# TT7N_v1_2.net
KiCad netlist of a schematic drawn in EAGLE
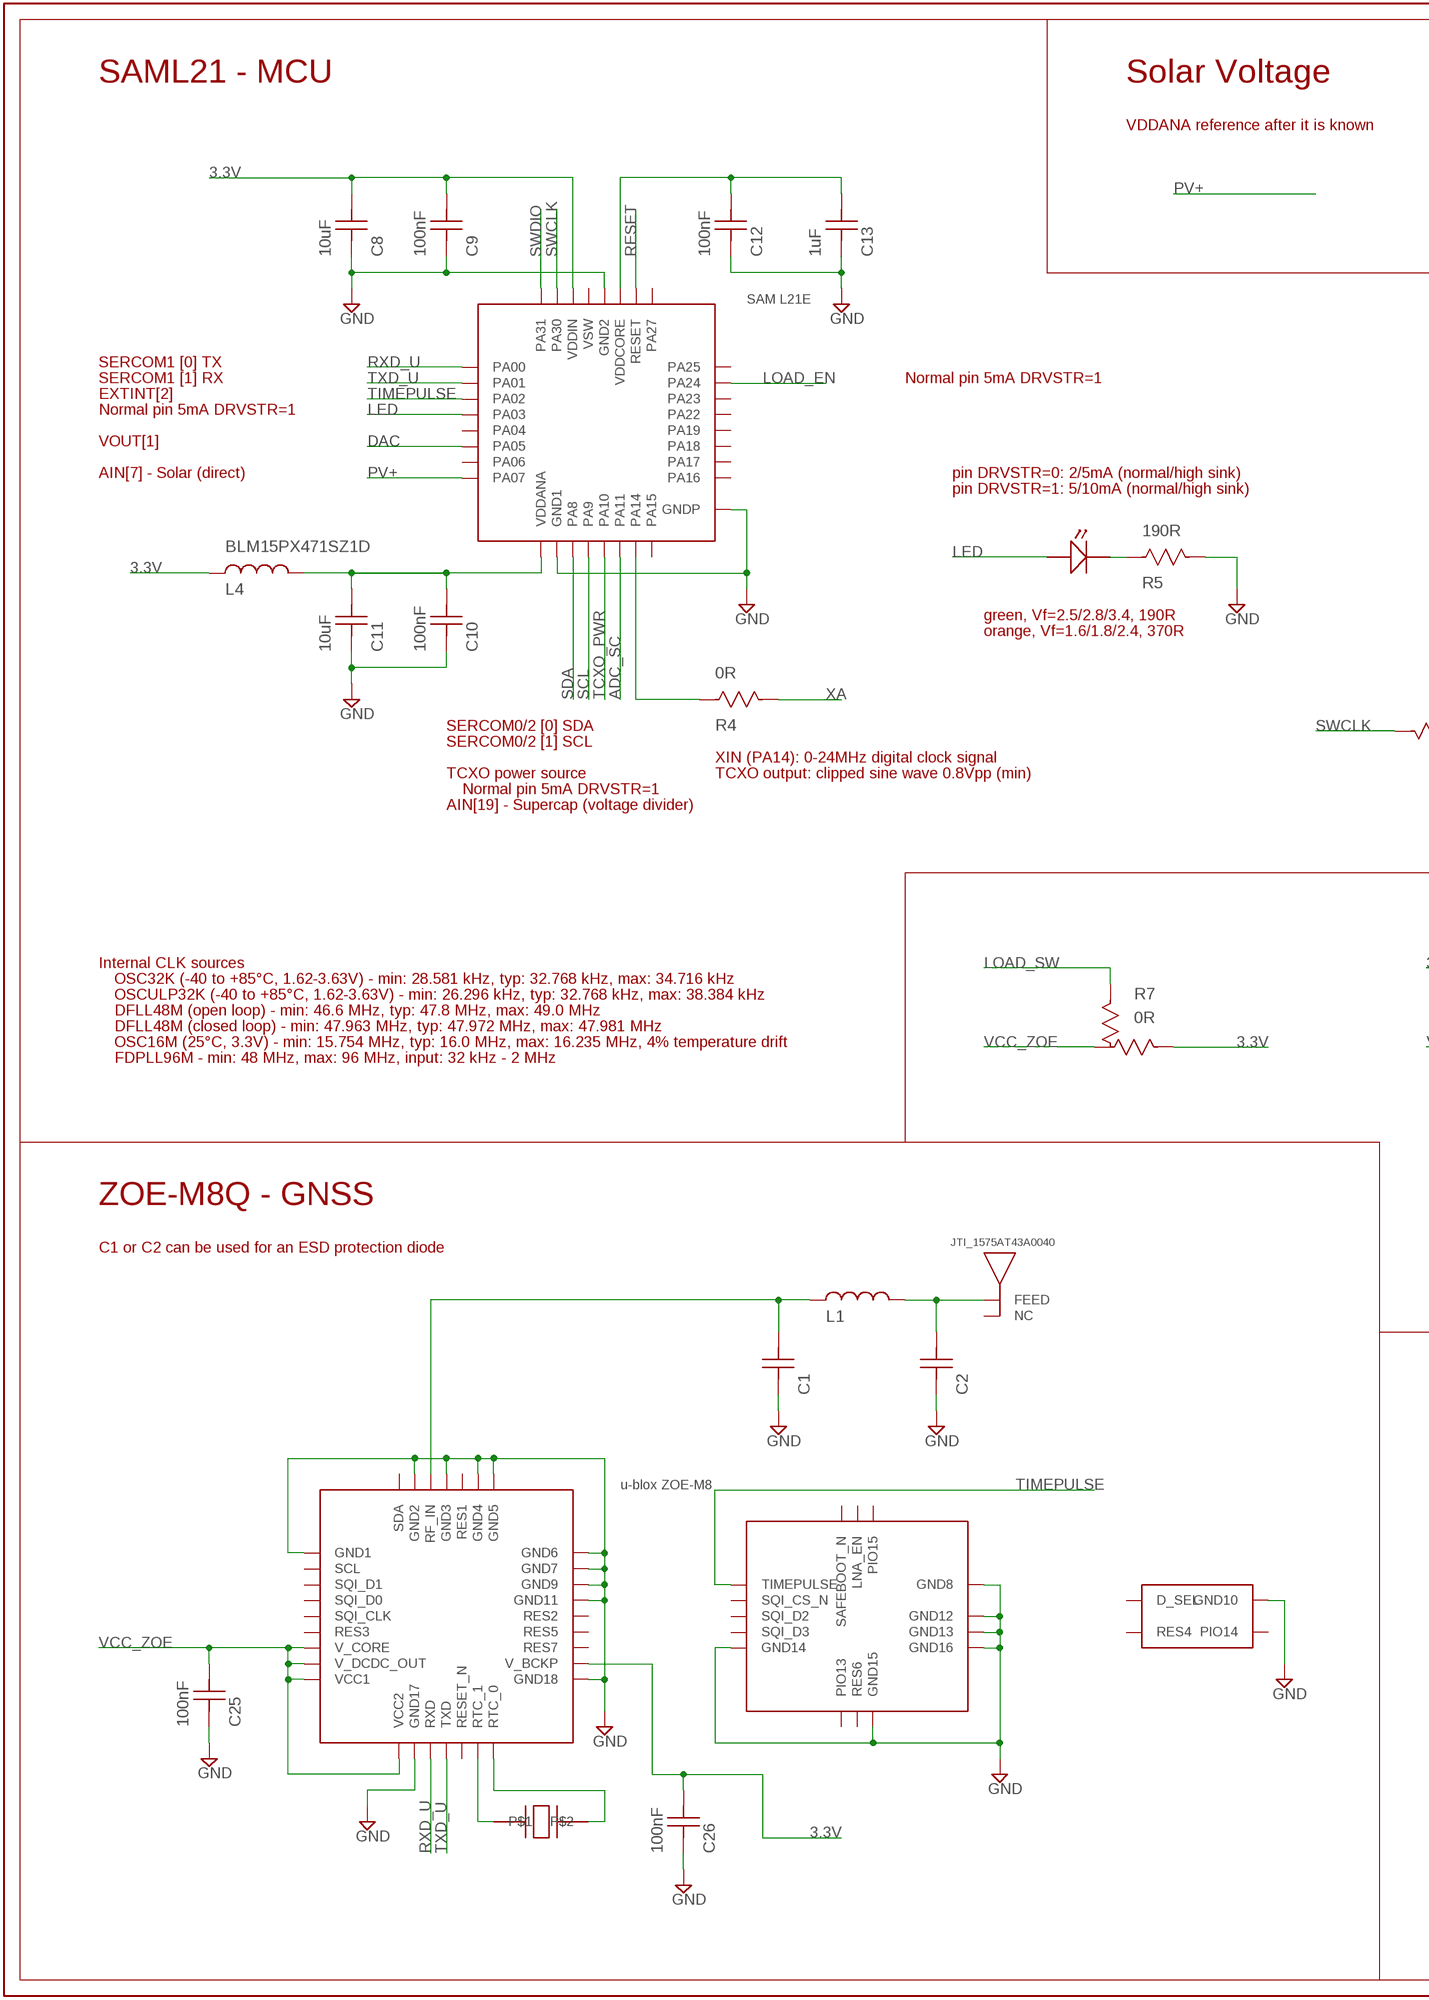
[diagram p0: schematic, sheet 1, part 1 of 2]
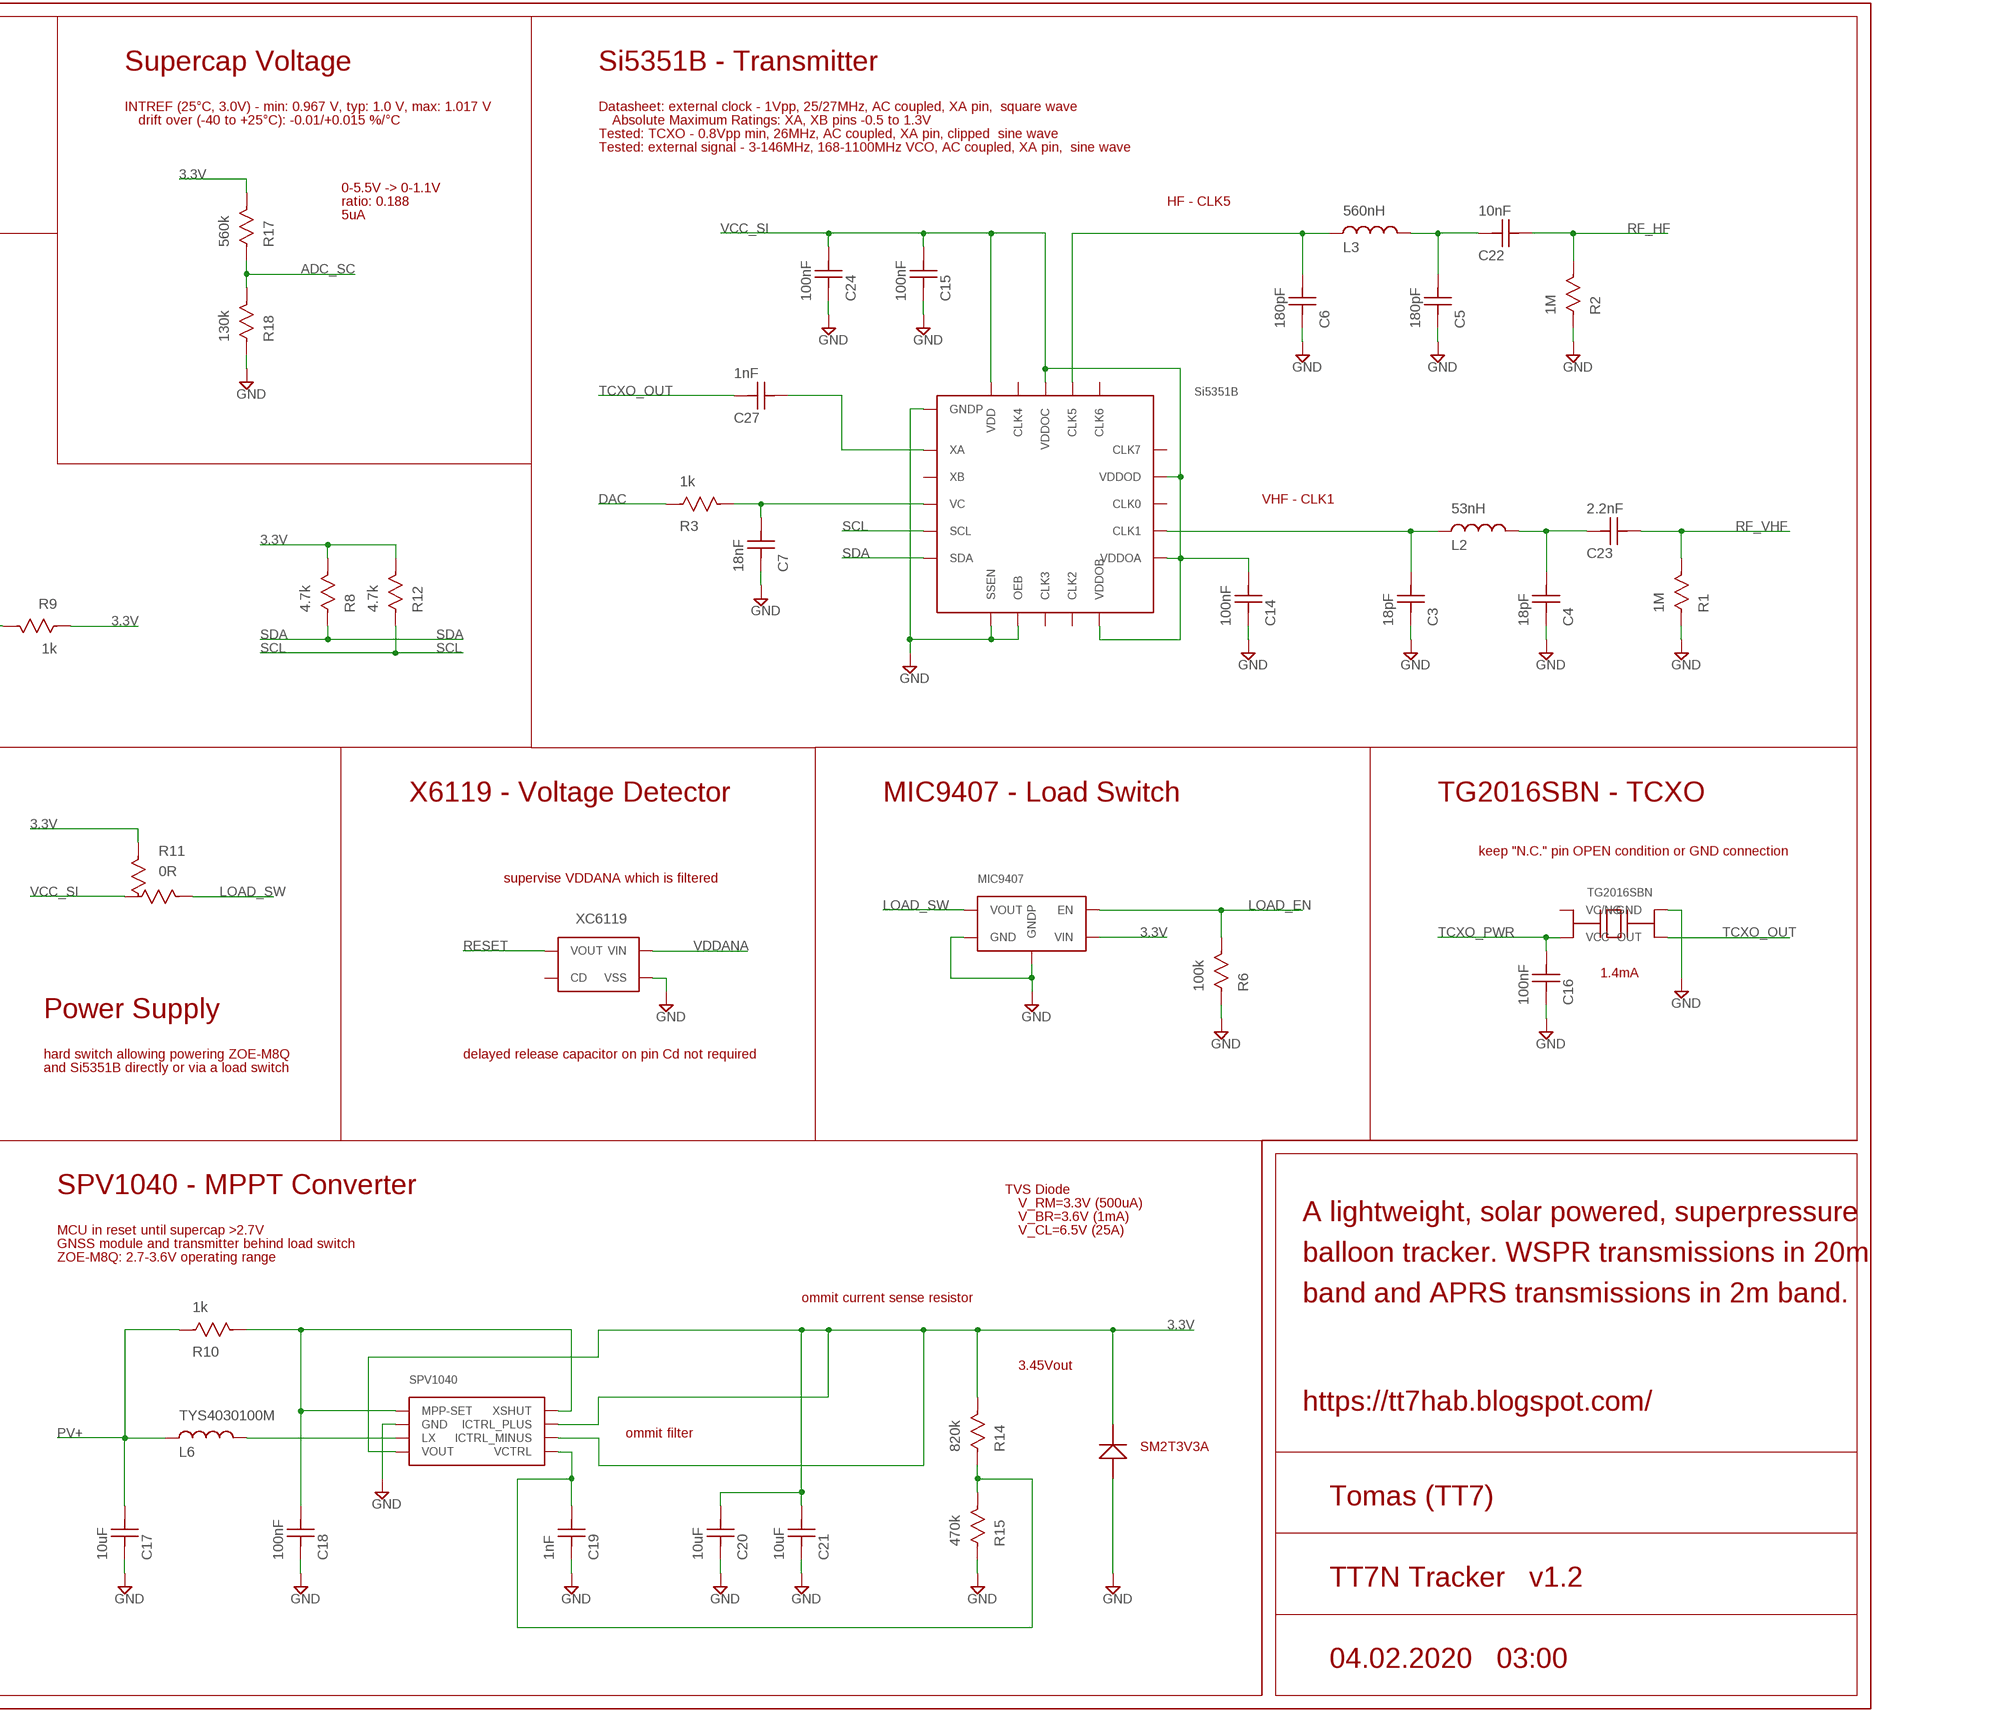
[diagram p1: schematic, sheet 1, part 2 of 2]

(export (version "E")
  (design (tool "Eeschema 10.0.6"))
  (components
    (comp (ref "ANT1")
      (value "JTI_1575AT43A0040")
      (footprint "eagle-import:JTI_1575AT43A0040")
      (libsource (lib "eagle-import") (part "JTI_1575AT43A0040"))
    )
    (comp (ref "C1")
      (value "CAP0402")
      (footprint "eagle-import:CAP0402")
      (libsource (lib "eagle-import") (part "CAP0402"))
    )
    (comp (ref "C2")
      (value "CAP0402")
      (footprint "eagle-import:CAP0402")
      (libsource (lib "eagle-import") (part "CAP0402"))
    )
    (comp (ref "C3")
      (value "18pF")
      (footprint "eagle-import:CAP0402")
      (libsource (lib "eagle-import") (part "CAP0402"))
    )
    (comp (ref "C4")
      (value "18pF")
      (footprint "eagle-import:CAP0402")
      (libsource (lib "eagle-import") (part "CAP0402"))
    )
    (comp (ref "C5")
      (value "180pF")
      (footprint "eagle-import:CAP0402")
      (libsource (lib "eagle-import") (part "CAP0402"))
    )
    (comp (ref "C6")
      (value "180pF")
      (footprint "eagle-import:CAP0402")
      (libsource (lib "eagle-import") (part "CAP0402"))
    )
    (comp (ref "C7")
      (value "18nF")
      (footprint "eagle-import:CAP0402")
      (libsource (lib "eagle-import") (part "CAP0402"))
    )
    (comp (ref "C8")
      (value "10uF")
      (footprint "eagle-import:CAP0402")
      (libsource (lib "eagle-import") (part "CAP0402"))
    )
    (comp (ref "C9")
      (value "100nF")
      (footprint "eagle-import:CAP0402")
      (libsource (lib "eagle-import") (part "CAP0402"))
    )
    (comp (ref "C10")
      (value "100nF")
      (footprint "eagle-import:CAP0402")
      (libsource (lib "eagle-import") (part "CAP0402"))
    )
    (comp (ref "C11")
      (value "10uF")
      (footprint "eagle-import:CAP0402")
      (libsource (lib "eagle-import") (part "CAP0402"))
    )
    (comp (ref "C12")
      (value "100nF")
      (footprint "eagle-import:CAP0402")
      (libsource (lib "eagle-import") (part "CAP0402"))
    )
    (comp (ref "C13")
      (value "1uF")
      (footprint "eagle-import:CAP0402")
      (libsource (lib "eagle-import") (part "CAP0402"))
    )
    (comp (ref "C14")
      (value "100nF")
      (footprint "eagle-import:CAP0402")
      (libsource (lib "eagle-import") (part "CAP0402"))
    )
    (comp (ref "C15")
      (value "100nF")
      (footprint "eagle-import:CAP0402")
      (libsource (lib "eagle-import") (part "CAP0402"))
    )
    (comp (ref "C16")
      (value "100nF")
      (footprint "eagle-import:CAP0402")
      (libsource (lib "eagle-import") (part "CAP0402"))
    )
    (comp (ref "C17")
      (value "10uF")
      (footprint "eagle-import:CAP0402")
      (libsource (lib "eagle-import") (part "CAP0402"))
    )
    (comp (ref "C18")
      (value "100nF")
      (footprint "eagle-import:CAP0402")
      (libsource (lib "eagle-import") (part "CAP0402"))
    )
    (comp (ref "C19")
      (value "1nF")
      (footprint "eagle-import:CAP0402")
      (libsource (lib "eagle-import") (part "CAP0402"))
    )
    (comp (ref "C20")
      (value "10uF")
      (footprint "eagle-import:CAP0402")
      (libsource (lib "eagle-import") (part "CAP0402"))
    )
    (comp (ref "C21")
      (value "10uF")
      (footprint "eagle-import:CAP0402")
      (libsource (lib "eagle-import") (part "CAP0402"))
    )
    (comp (ref "C22")
      (value "10nF")
      (footprint "eagle-import:CAP0402")
      (libsource (lib "eagle-import") (part "CAP0402"))
    )
    (comp (ref "C23")
      (value "2.2nF")
      (footprint "eagle-import:CAP0402")
      (libsource (lib "eagle-import") (part "CAP0402"))
    )
    (comp (ref "C24")
      (value "100nF")
      (footprint "eagle-import:CAP0402")
      (libsource (lib "eagle-import") (part "CAP0402"))
    )
    (comp (ref "C25")
      (value "100nF")
      (footprint "eagle-import:CAP0402")
      (libsource (lib "eagle-import") (part "CAP0402"))
    )
    (comp (ref "C26")
      (value "100nF")
      (footprint "eagle-import:CAP0402")
      (libsource (lib "eagle-import") (part "CAP0402"))
    )
    (comp (ref "C27")
      (value "1nF")
      (footprint "eagle-import:CAP0402")
      (libsource (lib "eagle-import") (part "CAP0402"))
    )
    (comp (ref "D1")
      (value "SM2T3V3A")
      (footprint "eagle-import:SM2T3V3A")
      (libsource (lib "eagle-import") (part "SM2T3V3A"))
    )
    (comp (ref "L1")
      (value "IND0402")
      (footprint "eagle-import:IND0402")
      (libsource (lib "eagle-import") (part "IND0402"))
    )
    (comp (ref "L2")
      (value "53nH")
      (footprint "eagle-import:IND0402")
      (libsource (lib "eagle-import") (part "IND0402"))
    )
    (comp (ref "L3")
      (value "560nH")
      (footprint "eagle-import:IND0402")
      (libsource (lib "eagle-import") (part "IND0402"))
    )
    (comp (ref "L4")
      (value "BLM15PX471SZ1D")
      (footprint "eagle-import:IND0402")
      (libsource (lib "eagle-import") (part "IND0402"))
    )
    (comp (ref "L6")
      (value "TYS4030100M")
      (footprint "eagle-import:TYS4030100M")
      (libsource (lib "eagle-import") (part "TYS4030100M"))
    )
    (comp (ref "LED1")
      (value "LED0603")
      (footprint "eagle-import:LED0603")
      (libsource (lib "eagle-import") (part "LED0603"))
    )
    (comp (ref "R1")
      (value "1M")
      (footprint "eagle-import:RES0402")
      (libsource (lib "eagle-import") (part "RES0402"))
    )
    (comp (ref "R2")
      (value "1M")
      (footprint "eagle-import:RES0402")
      (libsource (lib "eagle-import") (part "RES0402"))
    )
    (comp (ref "R3")
      (value "1k")
      (footprint "eagle-import:RES0402")
      (libsource (lib "eagle-import") (part "RES0402"))
    )
    (comp (ref "R4")
      (value "0R")
      (footprint "eagle-import:RES0402")
      (libsource (lib "eagle-import") (part "RES0402"))
    )
    (comp (ref "R5")
      (value "190R")
      (footprint "eagle-import:RES0402")
      (libsource (lib "eagle-import") (part "RES0402"))
    )
    (comp (ref "R6")
      (value "100k")
      (footprint "eagle-import:RES0402")
      (libsource (lib "eagle-import") (part "RES0402"))
    )
    (comp (ref "R7")
      (value "0R")
      (footprint "eagle-import:RES0402-3")
      (libsource (lib "eagle-import") (part "RES0402-3"))
    )
    (comp (ref "R8")
      (value "4.7k")
      (footprint "eagle-import:RES0402")
      (libsource (lib "eagle-import") (part "RES0402"))
    )
    (comp (ref "R9")
      (value "1k")
      (footprint "eagle-import:RES0402")
      (libsource (lib "eagle-import") (part "RES0402"))
    )
    (comp (ref "R10")
      (value "1k")
      (footprint "eagle-import:RES0402")
      (libsource (lib "eagle-import") (part "RES0402"))
    )
    (comp (ref "R11")
      (value "0R")
      (footprint "eagle-import:RES0402-3")
      (libsource (lib "eagle-import") (part "RES0402-3"))
    )
    (comp (ref "R12")
      (value "4.7k")
      (footprint "eagle-import:RES0402")
      (libsource (lib "eagle-import") (part "RES0402"))
    )
    (comp (ref "R14")
      (value "820k")
      (footprint "eagle-import:RES0402")
      (libsource (lib "eagle-import") (part "RES0402"))
    )
    (comp (ref "R15")
      (value "470k")
      (footprint "eagle-import:RES0402")
      (libsource (lib "eagle-import") (part "RES0402"))
    )
    (comp (ref "R17")
      (value "560k")
      (footprint "eagle-import:RES0402")
      (libsource (lib "eagle-import") (part "RES0402"))
    )
    (comp (ref "R18")
      (value "130k")
      (footprint "eagle-import:RES0402")
      (libsource (lib "eagle-import") (part "RES0402"))
    )
    (comp (ref "TCXO1")
      (value "TG2016SBN")
      (footprint "eagle-import:TG2016SBN")
      (libsource (lib "eagle-import") (part "TG2016SBN"))
    )
    (comp (ref "U1")
      (value "SPV1040")
      (footprint "eagle-import:SPV1040")
      (libsource (lib "eagle-import") (part "SPV1040"))
    )
    (comp (ref "U2")
      (value "SAML21E18B-MUT")
      (footprint "eagle-import:SAML21E18B-MUT")
      (libsource (lib "eagle-import") (part "SAML21E18B-MUT"))
    )
    (comp (ref "U3")
      (value "XC6119")
      (footprint "eagle-import:XC6119")
      (libsource (lib "eagle-import") (part "XC6119"))
    )
    (comp (ref "U4")
      (value "UBLOX_ZOE-M8")
      (footprint "eagle-import:UBLOX_ZOE-M8")
      (libsource (lib "eagle-import") (part "UBLOX_ZOE-M8"))
    )
    (comp (ref "U5")
      (value "SI5351B")
      (footprint "eagle-import:SI5351B")
      (libsource (lib "eagle-import") (part "SI5351B"))
    )
    (comp (ref "U6")
      (value "MIC9407")
      (footprint "eagle-import:MIC9407")
      (libsource (lib "eagle-import") (part "MIC9407"))
    )
    (comp (ref "U7")
      (value "CM8V-T1A")
      (footprint "eagle-import:CM8V-T1A")
      (libsource (lib "eagle-import") (part "CM8V-T1A"))
    )
  )
  (nets
    (net (code "1") (name "/3.3V") (class "Default")
      (node (ref "C20") (pin "P$2") (pinfunction "P$2_P$2") (pintype "bidirectional"))
      (node (ref "C21") (pin "P$2") (pinfunction "P$2_P$2") (pintype "bidirectional"))
      (node (ref "C26") (pin "P$2") (pinfunction "P$2_P$2") (pintype "bidirectional"))
      (node (ref "C8") (pin "P$2") (pinfunction "P$2_P$2") (pintype "bidirectional"))
      (node (ref "C9") (pin "P$2") (pinfunction "P$2_P$2") (pintype "bidirectional"))
      (node (ref "D1") (pin "CATHODE") (pinfunction "CATHODE_CATHODE") (pintype "bidirectional"))
      (node (ref "L4") (pin "P$1") (pinfunction "P$1_P$1") (pintype "bidirectional"))
      (node (ref "R11") (pin "1") (pinfunction "1_1") (pintype "bidirectional"))
      (node (ref "R12") (pin "P$2") (pinfunction "P$2_P$2") (pintype "bidirectional"))
      (node (ref "R14") (pin "P$2") (pinfunction "P$2_P$2") (pintype "bidirectional"))
      (node (ref "R17") (pin "P$2") (pinfunction "P$2_P$2") (pintype "bidirectional"))
      (node (ref "R7") (pin "3") (pinfunction "3_3") (pintype "bidirectional"))
      (node (ref "R8") (pin "P$2") (pinfunction "P$2_P$2") (pintype "bidirectional"))
      (node (ref "R9") (pin "P$1") (pinfunction "P$1_P$1") (pintype "bidirectional"))
      (node (ref "U1") (pin "ICTRL_MINUS") (pinfunction "ICTRL_MINUS_ICTRL_MINUS") (pintype "bidirectional"))
      (node (ref "U1") (pin "ICTRL_PLUS") (pinfunction "ICTRL_PLUS_ICTRL_PLUS") (pintype "bidirectional"))
      (node (ref "U1") (pin "VOUT") (pinfunction "VOUT_VOUT") (pintype "bidirectional"))
      (node (ref "U2") (pin "VDDIN") (pinfunction "VDDIN_VDDIN") (pintype "bidirectional"))
      (node (ref "U4") (pin "V_BCKP") (pinfunction "V_BCKP_V_BCKP") (pintype "bidirectional"))
      (node (ref "U6") (pin "VIN") (pinfunction "VIN_VIN") (pintype "bidirectional"))
    )
    (net (code "2") (name "/ADC_SC") (class "Default")
      (node (ref "R17") (pin "P$1") (pinfunction "P$1_P$1") (pintype "bidirectional"))
      (node (ref "R18") (pin "P$2") (pinfunction "P$2_P$2") (pintype "bidirectional"))
      (node (ref "U2") (pin "PA11") (pinfunction "PA11_PA11") (pintype "bidirectional"))
    )
    (net (code "3") (name "/DAC") (class "Default")
      (node (ref "R3") (pin "P$1") (pinfunction "P$1_P$1") (pintype "bidirectional"))
      (node (ref "U2") (pin "PA05") (pinfunction "PA05_PA05") (pintype "bidirectional"))
    )
    (net (code "4") (name "/LED") (class "Default")
      (node (ref "LED1") (pin "ANODE") (pinfunction "ANODE_ANODE") (pintype "bidirectional"))
      (node (ref "U2") (pin "PA03") (pinfunction "PA03_PA03") (pintype "bidirectional"))
    )
    (net (code "5") (name "/LOAD_EN") (class "Default")
      (node (ref "R6") (pin "P$2") (pinfunction "P$2_P$2") (pintype "bidirectional"))
      (node (ref "U2") (pin "PA24") (pinfunction "PA24_PA24") (pintype "bidirectional"))
      (node (ref "U6") (pin "EN") (pinfunction "EN_EN") (pintype "bidirectional"))
    )
    (net (code "6") (name "/LOAD_SW") (class "Default")
      (node (ref "R11") (pin "3") (pinfunction "3_3") (pintype "bidirectional"))
      (node (ref "R7") (pin "1") (pinfunction "1_1") (pintype "bidirectional"))
      (node (ref "U6") (pin "VOUT") (pinfunction "VOUT_VOUT") (pintype "bidirectional"))
    )
    (net (code "7") (name "/PV+") (class "Default")
      (node (ref "C17") (pin "P$2") (pinfunction "P$2_P$2") (pintype "bidirectional"))
      (node (ref "L6") (pin "P1") (pinfunction "P$1_P1") (pintype "bidirectional"))
      (node (ref "R10") (pin "P$1") (pinfunction "P$1_P$1") (pintype "bidirectional"))
      (node (ref "U2") (pin "PA07") (pinfunction "PA07_PA07") (pintype "bidirectional"))
    )
    (net (code "8") (name "/RESET") (class "Default")
      (node (ref "U2") (pin "RESET") (pinfunction "RESET_RESET") (pintype "bidirectional"))
      (node (ref "U3") (pin "VOUT") (pinfunction "VOUT_VOUT") (pintype "bidirectional"))
    )
    (net (code "9") (name "/RF_HF") (class "Default")
      (node (ref "C22") (pin "P$2") (pinfunction "P$2_P$2") (pintype "bidirectional"))
      (node (ref "R2") (pin "P$2") (pinfunction "P$2_P$2") (pintype "bidirectional"))
    )
    (net (code "10") (name "/RF_VHF") (class "Default")
      (node (ref "C23") (pin "P$2") (pinfunction "P$2_P$2") (pintype "bidirectional"))
      (node (ref "R1") (pin "P$2") (pinfunction "P$2_P$2") (pintype "bidirectional"))
    )
    (net (code "11") (name "/RXD_U") (class "Default")
      (node (ref "U2") (pin "PA00") (pinfunction "PA00_PA00") (pintype "bidirectional"))
      (node (ref "U4") (pin "RXD") (pinfunction "RXD_RXD") (pintype "bidirectional"))
    )
    (net (code "12") (name "/SCL") (class "Default")
      (node (ref "R12") (pin "P$1") (pinfunction "P$1_P$1") (pintype "bidirectional"))
      (node (ref "U2") (pin "PA09") (pinfunction "PA9_PA09") (pintype "bidirectional"))
      (node (ref "U5") (pin "SCL") (pinfunction "SCL_SCL") (pintype "bidirectional"))
    )
    (net (code "13") (name "/SDA") (class "Default")
      (node (ref "R8") (pin "P$1") (pinfunction "P$1_P$1") (pintype "bidirectional"))
      (node (ref "U2") (pin "PA08") (pinfunction "PA8_PA08") (pintype "bidirectional"))
      (node (ref "U5") (pin "SDA") (pinfunction "SDA_SDA") (pintype "bidirectional"))
    )
    (net (code "14") (name "/SWCLK") (class "Default")
      (node (ref "R9") (pin "P$2") (pinfunction "P$2_P$2") (pintype "bidirectional"))
      (node (ref "U2") (pin "PA30") (pinfunction "PA30_PA30") (pintype "bidirectional"))
    )
    (net (code "15") (name "/SWDIO") (class "Default")
      (node (ref "U2") (pin "PA31") (pinfunction "PA31_PA31") (pintype "bidirectional"))
    )
    (net (code "16") (name "/TCXO_OUT") (class "Default")
      (node (ref "C27") (pin "P$1") (pinfunction "P$1_P$1") (pintype "bidirectional"))
      (node (ref "TCXO1") (pin "OUT") (pinfunction "OUT_OUT") (pintype "bidirectional"))
    )
    (net (code "17") (name "/TCXO_PWR") (class "Default")
      (node (ref "C16") (pin "P$2") (pinfunction "P$2_P$2") (pintype "bidirectional"))
      (node (ref "TCXO1") (pin "VCC") (pinfunction "VCC_VCC") (pintype "bidirectional"))
      (node (ref "U2") (pin "PA10") (pinfunction "PA10_PA10") (pintype "bidirectional"))
    )
    (net (code "18") (name "/TIMEPULSE") (class "Default")
      (node (ref "U2") (pin "PA02") (pinfunction "PA02_PA02") (pintype "bidirectional"))
      (node (ref "U4") (pin "TIMEPULSE") (pinfunction "TIMEPULSE_TIMEPULSE") (pintype "bidirectional"))
    )
    (net (code "19") (name "/TXD_U") (class "Default")
      (node (ref "U2") (pin "PA01") (pinfunction "PA01_PA01") (pintype "bidirectional"))
      (node (ref "U4") (pin "TXD") (pinfunction "TXD_TXD") (pintype "bidirectional"))
    )
    (net (code "20") (name "/VCC_SI") (class "Default")
      (node (ref "C14") (pin "P$2") (pinfunction "P$2_P$2") (pintype "bidirectional"))
      (node (ref "C15") (pin "P$2") (pinfunction "P$2_P$2") (pintype "bidirectional"))
      (node (ref "C24") (pin "P$2") (pinfunction "P$2_P$2") (pintype "bidirectional"))
      (node (ref "R11") (pin "2") (pinfunction "2_2") (pintype "bidirectional"))
      (node (ref "U5") (pin "VDD") (pinfunction "VDD_VDD") (pintype "bidirectional"))
      (node (ref "U5") (pin "VDDOA") (pinfunction "VDDOA_VDDOA") (pintype "bidirectional"))
      (node (ref "U5") (pin "VDDOB") (pinfunction "VDDOB_VDDOB") (pintype "bidirectional"))
      (node (ref "U5") (pin "VDDOC") (pinfunction "VDDOC_VDDOC") (pintype "bidirectional"))
      (node (ref "U5") (pin "VDDOD") (pinfunction "VDDOD_VDDOD") (pintype "bidirectional"))
    )
    (net (code "21") (name "/VCC_ZOE") (class "Default")
      (node (ref "C25") (pin "P$2") (pinfunction "P$2_P$2") (pintype "bidirectional"))
      (node (ref "R7") (pin "2") (pinfunction "2_2") (pintype "bidirectional"))
      (node (ref "U4") (pin "VCC1") (pinfunction "VCC1_VCC1") (pintype "bidirectional"))
      (node (ref "U4") (pin "VCC2") (pinfunction "VCC2_VCC2") (pintype "bidirectional"))
      (node (ref "U4") (pin "V_CORE") (pinfunction "V_CORE_V_CORE") (pintype "bidirectional"))
      (node (ref "U4") (pin "V_DCDC_OUT") (pinfunction "V_DCDC_OUT_V_DCDC_OUT") (pintype "bidirectional"))
    )
    (net (code "22") (name "/VDDANA") (class "Default")
      (node (ref "C10") (pin "P$2") (pinfunction "P$2_P$2") (pintype "bidirectional"))
      (node (ref "C11") (pin "P$2") (pinfunction "P$2_P$2") (pintype "bidirectional"))
      (node (ref "L4") (pin "P$2") (pinfunction "P$2_P$2") (pintype "bidirectional"))
      (node (ref "U2") (pin "VDDANA") (pinfunction "VDDANA_VDDANA") (pintype "bidirectional"))
      (node (ref "U3") (pin "VIN") (pinfunction "VIN_VIN") (pintype "bidirectional"))
    )
    (net (code "23") (name "/XA") (class "Default")
      (node (ref "C27") (pin "P$2") (pinfunction "P$2_P$2") (pintype "bidirectional"))
      (node (ref "R4") (pin "P$2") (pinfunction "P$2_P$2") (pintype "bidirectional"))
      (node (ref "U5") (pin "XA") (pinfunction "XA_XA") (pintype "bidirectional"))
    )
    (net (code "24") (name "GND") (class "Default")
      (node (ref "C1") (pin "P$1") (pinfunction "P$1_P$1") (pintype "bidirectional"))
      (node (ref "C10") (pin "P$1") (pinfunction "P$1_P$1") (pintype "bidirectional"))
      (node (ref "C11") (pin "P$1") (pinfunction "P$1_P$1") (pintype "bidirectional"))
      (node (ref "C12") (pin "P$1") (pinfunction "P$1_P$1") (pintype "bidirectional"))
      (node (ref "C13") (pin "P$1") (pinfunction "P$1_P$1") (pintype "bidirectional"))
      (node (ref "C14") (pin "P$1") (pinfunction "P$1_P$1") (pintype "bidirectional"))
      (node (ref "C15") (pin "P$1") (pinfunction "P$1_P$1") (pintype "bidirectional"))
      (node (ref "C16") (pin "P$1") (pinfunction "P$1_P$1") (pintype "bidirectional"))
      (node (ref "C17") (pin "P$1") (pinfunction "P$1_P$1") (pintype "bidirectional"))
      (node (ref "C18") (pin "P$1") (pinfunction "P$1_P$1") (pintype "bidirectional"))
      (node (ref "C19") (pin "P$1") (pinfunction "P$1_P$1") (pintype "bidirectional"))
      (node (ref "C2") (pin "P$1") (pinfunction "P$1_P$1") (pintype "bidirectional"))
      (node (ref "C20") (pin "P$1") (pinfunction "P$1_P$1") (pintype "bidirectional"))
      (node (ref "C21") (pin "P$1") (pinfunction "P$1_P$1") (pintype "bidirectional"))
      (node (ref "C24") (pin "P$1") (pinfunction "P$1_P$1") (pintype "bidirectional"))
      (node (ref "C25") (pin "P$1") (pinfunction "P$1_P$1") (pintype "bidirectional"))
      (node (ref "C26") (pin "P$1") (pinfunction "P$1_P$1") (pintype "bidirectional"))
      (node (ref "C3") (pin "P$1") (pinfunction "P$1_P$1") (pintype "bidirectional"))
      (node (ref "C4") (pin "P$1") (pinfunction "P$1_P$1") (pintype "bidirectional"))
      (node (ref "C5") (pin "P$1") (pinfunction "P$1_P$1") (pintype "bidirectional"))
      (node (ref "C6") (pin "P$1") (pinfunction "P$1_P$1") (pintype "bidirectional"))
      (node (ref "C7") (pin "P$1") (pinfunction "P$1_P$1") (pintype "bidirectional"))
      (node (ref "C8") (pin "P$1") (pinfunction "P$1_P$1") (pintype "bidirectional"))
      (node (ref "C9") (pin "P$1") (pinfunction "P$1_P$1") (pintype "bidirectional"))
      (node (ref "D1") (pin "ANODE") (pinfunction "ANODE_ANODE") (pintype "bidirectional"))
      (node (ref "R1") (pin "P$1") (pinfunction "P$1_P$1") (pintype "bidirectional"))
      (node (ref "R15") (pin "P$1") (pinfunction "P$1_P$1") (pintype "bidirectional"))
      (node (ref "R18") (pin "P$1") (pinfunction "P$1_P$1") (pintype "bidirectional"))
      (node (ref "R2") (pin "P$1") (pinfunction "P$1_P$1") (pintype "bidirectional"))
      (node (ref "R5") (pin "P$2") (pinfunction "P$2_P$2") (pintype "bidirectional"))
      (node (ref "R6") (pin "P$1") (pinfunction "P$1_P$1") (pintype "bidirectional"))
      (node (ref "TCXO1") (pin "GND") (pinfunction "GND_GND") (pintype "bidirectional"))
      (node (ref "U1") (pin "GND") (pinfunction "GND_GND") (pintype "bidirectional"))
      (node (ref "U2") (pin "GND1") (pinfunction "GND1_GND1") (pintype "bidirectional"))
      (node (ref "U2") (pin "GND2") (pinfunction "GND2_GND2") (pintype "bidirectional"))
      (node (ref "U2") (pin "GNDP") (pinfunction "GNDP_GNDP") (pintype "bidirectional"))
      (node (ref "U3") (pin "VSS") (pinfunction "VSS_VSS") (pintype "bidirectional"))
      (node (ref "U4") (pin "GND1") (pinfunction "GND1_GND1") (pintype "bidirectional"))
      (node (ref "U4") (pin "GND10") (pinfunction "GND10_GND10") (pintype "bidirectional"))
      (node (ref "U4") (pin "GND11") (pinfunction "GND11_GND11") (pintype "bidirectional"))
      (node (ref "U4") (pin "GND12") (pinfunction "GND12_GND12") (pintype "bidirectional"))
      (node (ref "U4") (pin "GND13") (pinfunction "GND13_GND13") (pintype "bidirectional"))
      (node (ref "U4") (pin "GND14") (pinfunction "GND14_GND14") (pintype "bidirectional"))
      (node (ref "U4") (pin "GND15") (pinfunction "GND15_GND15") (pintype "bidirectional"))
      (node (ref "U4") (pin "GND16") (pinfunction "GND16_GND16") (pintype "bidirectional"))
      (node (ref "U4") (pin "GND17") (pinfunction "GND17_GND17") (pintype "bidirectional"))
      (node (ref "U4") (pin "GND18") (pinfunction "GND18_GND18") (pintype "bidirectional"))
      (node (ref "U4") (pin "GND2") (pinfunction "GND2_GND2") (pintype "bidirectional"))
      (node (ref "U4") (pin "GND3") (pinfunction "GND3_GND3") (pintype "bidirectional"))
      (node (ref "U4") (pin "GND4") (pinfunction "GND4_GND4") (pintype "bidirectional"))
      (node (ref "U4") (pin "GND5") (pinfunction "GND5_GND5") (pintype "bidirectional"))
      (node (ref "U4") (pin "GND6") (pinfunction "GND6_GND6") (pintype "bidirectional"))
      (node (ref "U4") (pin "GND7") (pinfunction "GND7_GND7") (pintype "bidirectional"))
      (node (ref "U4") (pin "GND8") (pinfunction "GND8_GND8") (pintype "bidirectional"))
      (node (ref "U4") (pin "GND9") (pinfunction "GND9_GND9") (pintype "bidirectional"))
      (node (ref "U5") (pin "GNDP") (pinfunction "GNDP_GNDP") (pintype "bidirectional"))
      (node (ref "U5") (pin "OEB") (pinfunction "OEB_OEB") (pintype "bidirectional"))
      (node (ref "U5") (pin "SSEN") (pinfunction "SSEN_SSEN") (pintype "bidirectional"))
      (node (ref "U6") (pin "GND") (pinfunction "GND_GND") (pintype "bidirectional"))
      (node (ref "U6") (pin "GNDP") (pinfunction "GNDP_GNDP") (pintype "bidirectional"))
    )
    (net (code "25") (name "Net-(ANT1-PadFEED)") (class "Default")
      (node (ref "ANT1") (pin "FEED") (pinfunction "FEED_FEED") (pintype "bidirectional"))
      (node (ref "C2") (pin "P$2") (pinfunction "P$2_P$2") (pintype "bidirectional"))
      (node (ref "L1") (pin "P$2") (pinfunction "P$2_P$2") (pintype "bidirectional"))
    )
    (net (code "26") (name "Net-(C1-PadP$2)") (class "Default")
      (node (ref "C1") (pin "P$2") (pinfunction "P$2_P$2") (pintype "bidirectional"))
      (node (ref "L1") (pin "P$1") (pinfunction "P$1_P$1") (pintype "bidirectional"))
      (node (ref "U4") (pin "RF_IN") (pinfunction "RF_IN_RF_IN") (pintype "bidirectional"))
    )
    (net (code "27") (name "Net-(C3-PadP$2)") (class "Default")
      (node (ref "C3") (pin "P$2") (pinfunction "P$2_P$2") (pintype "bidirectional"))
      (node (ref "L2") (pin "P$1") (pinfunction "P$1_P$1") (pintype "bidirectional"))
      (node (ref "U5") (pin "CLK1") (pinfunction "CLK1_CLK1") (pintype "bidirectional"))
    )
    (net (code "28") (name "Net-(C6-PadP$2)") (class "Default")
      (node (ref "C6") (pin "P$2") (pinfunction "P$2_P$2") (pintype "bidirectional"))
      (node (ref "L3") (pin "P$1") (pinfunction "P$1_P$1") (pintype "bidirectional"))
      (node (ref "U5") (pin "CLK5") (pinfunction "CLK5_CLK5") (pintype "bidirectional"))
    )
    (net (code "29") (name "Net-(C7-PadP$2)") (class "Default")
      (node (ref "C7") (pin "P$2") (pinfunction "P$2_P$2") (pintype "bidirectional"))
      (node (ref "R3") (pin "P$2") (pinfunction "P$2_P$2") (pintype "bidirectional"))
      (node (ref "U5") (pin "VC") (pinfunction "VC_VC") (pintype "bidirectional"))
    )
    (net (code "30") (name "Net-(C12-PadP$2)") (class "Default")
      (node (ref "C12") (pin "P$2") (pinfunction "P$2_P$2") (pintype "bidirectional"))
      (node (ref "C13") (pin "P$2") (pinfunction "P$2_P$2") (pintype "bidirectional"))
      (node (ref "U2") (pin "VDDCORE") (pinfunction "VDDCORE_VDDCORE") (pintype "bidirectional"))
    )
    (net (code "31") (name "Net-(C18-PadP$2)") (class "Default")
      (node (ref "C18") (pin "P$2") (pinfunction "P$2_P$2") (pintype "bidirectional"))
      (node (ref "R10") (pin "P$2") (pinfunction "P$2_P$2") (pintype "bidirectional"))
      (node (ref "U1") (pin "MPP-SET") (pinfunction "MPP-SET_MPP-SET") (pintype "bidirectional"))
      (node (ref "U1") (pin "XSHUT") (pinfunction "XSHUT_XSHUT") (pintype "bidirectional"))
    )
    (net (code "32") (name "Net-(C19-PadP$2)") (class "Default")
      (node (ref "C19") (pin "P$2") (pinfunction "P$2_P$2") (pintype "bidirectional"))
      (node (ref "R14") (pin "P$1") (pinfunction "P$1_P$1") (pintype "bidirectional"))
      (node (ref "R15") (pin "P$2") (pinfunction "P$2_P$2") (pintype "bidirectional"))
      (node (ref "U1") (pin "VCTRL") (pinfunction "VCTRL_VCTRL") (pintype "bidirectional"))
    )
    (net (code "33") (name "Net-(C22-PadP$1)") (class "Default")
      (node (ref "C22") (pin "P$1") (pinfunction "P$1_P$1") (pintype "bidirectional"))
      (node (ref "C5") (pin "P$2") (pinfunction "P$2_P$2") (pintype "bidirectional"))
      (node (ref "L3") (pin "P$2") (pinfunction "P$2_P$2") (pintype "bidirectional"))
    )
    (net (code "34") (name "Net-(C23-PadP$1)") (class "Default")
      (node (ref "C23") (pin "P$1") (pinfunction "P$1_P$1") (pintype "bidirectional"))
      (node (ref "C4") (pin "P$2") (pinfunction "P$2_P$2") (pintype "bidirectional"))
      (node (ref "L2") (pin "P$2") (pinfunction "P$2_P$2") (pintype "bidirectional"))
    )
    (net (code "35") (name "Net-(L6-P$2)") (class "Default")
      (node (ref "L6") (pin "P2") (pinfunction "P$2_P2") (pintype "bidirectional"))
      (node (ref "U1") (pin "LX") (pinfunction "LX_LX") (pintype "bidirectional"))
    )
    (net (code "36") (name "Net-(LED1-PadCATHODE)") (class "Default")
      (node (ref "LED1") (pin "CATHODE") (pinfunction "CATHODE_CATHODE") (pintype "bidirectional"))
      (node (ref "R5") (pin "P$1") (pinfunction "P$1_P$1") (pintype "bidirectional"))
    )
    (net (code "37") (name "Net-(R4-PadP$1)") (class "Default")
      (node (ref "R4") (pin "P$1") (pinfunction "P$1_P$1") (pintype "bidirectional"))
      (node (ref "U2") (pin "PA14") (pinfunction "PA14_PA14") (pintype "bidirectional"))
    )
    (net (code "38") (name "Net-(U4-PadRTC_0)") (class "Default")
      (node (ref "U4") (pin "RTC_0") (pinfunction "RTC_0_RTC_0") (pintype "bidirectional"))
      (node (ref "U7") (pin "P$2") (pinfunction "P$2_P$2") (pintype "bidirectional"))
    )
    (net (code "39") (name "Net-(U4-PadRTC_1)") (class "Default")
      (node (ref "U4") (pin "RTC_1") (pinfunction "RTC_1_RTC_1") (pintype "bidirectional"))
      (node (ref "U7") (pin "P$1") (pinfunction "P$1_P$1") (pintype "bidirectional"))
    )
    (net (code "40") (name "unconnected-(ANT1-PadNC)") (class "Default")
      (node (ref "ANT1") (pin "NC") (pinfunction "NC_NC") (pintype "bidirectional"))
    )
    (net (code "41") (name "unconnected-(TCXO1-PadVC{slash}NC)") (class "Default")
      (node (ref "TCXO1") (pin "VC/NC") (pinfunction "VC/NC_VC/NC") (pintype "bidirectional"))
    )
    (net (code "42") (name "unconnected-(U2-PadPA04)") (class "Default")
      (node (ref "U2") (pin "PA04") (pinfunction "PA04_PA04") (pintype "bidirectional"))
    )
    (net (code "43") (name "unconnected-(U2-PadPA06)") (class "Default")
      (node (ref "U2") (pin "PA06") (pinfunction "PA06_PA06") (pintype "bidirectional"))
    )
    (net (code "44") (name "unconnected-(U2-PadPA15)") (class "Default")
      (node (ref "U2") (pin "PA15") (pinfunction "PA15_PA15") (pintype "bidirectional"))
    )
    (net (code "45") (name "unconnected-(U2-PadPA16)") (class "Default")
      (node (ref "U2") (pin "PA16") (pinfunction "PA16_PA16") (pintype "bidirectional"))
    )
    (net (code "46") (name "unconnected-(U2-PadPA17)") (class "Default")
      (node (ref "U2") (pin "PA17") (pinfunction "PA17_PA17") (pintype "bidirectional"))
    )
    (net (code "47") (name "unconnected-(U2-PadPA18)") (class "Default")
      (node (ref "U2") (pin "PA18") (pinfunction "PA18_PA18") (pintype "bidirectional"))
    )
    (net (code "48") (name "unconnected-(U2-PadPA19)") (class "Default")
      (node (ref "U2") (pin "PA19") (pinfunction "PA19_PA19") (pintype "bidirectional"))
    )
    (net (code "49") (name "unconnected-(U2-PadPA22)") (class "Default")
      (node (ref "U2") (pin "PA22") (pinfunction "PA22_PA22") (pintype "bidirectional"))
    )
    (net (code "50") (name "unconnected-(U2-PadPA23)") (class "Default")
      (node (ref "U2") (pin "PA23") (pinfunction "PA23_PA23") (pintype "bidirectional"))
    )
    (net (code "51") (name "unconnected-(U2-PadPA25)") (class "Default")
      (node (ref "U2") (pin "PA25") (pinfunction "PA25_PA25") (pintype "bidirectional"))
    )
    (net (code "52") (name "unconnected-(U2-PadPA27)") (class "Default")
      (node (ref "U2") (pin "PA27") (pinfunction "PA27_PA27") (pintype "bidirectional"))
    )
    (net (code "53") (name "unconnected-(U2-PadVSW)") (class "Default")
      (node (ref "U2") (pin "VSW") (pinfunction "VSW_VSW") (pintype "bidirectional"))
    )
    (net (code "54") (name "unconnected-(U3-PadCD)") (class "Default")
      (node (ref "U3") (pin "CD") (pinfunction "CD_CD") (pintype "bidirectional"))
    )
    (net (code "55") (name "unconnected-(U4-PadD_SEL)") (class "Default")
      (node (ref "U4") (pin "D_SEL") (pinfunction "D_SEL_D_SEL") (pintype "bidirectional"))
    )
    (net (code "56") (name "unconnected-(U4-PadLNA_EN)") (class "Default")
      (node (ref "U4") (pin "LNA_EN") (pinfunction "LNA_EN_LNA_EN") (pintype "bidirectional"))
    )
    (net (code "57") (name "unconnected-(U4-PadPIO13)") (class "Default")
      (node (ref "U4") (pin "PIO13") (pinfunction "PIO13_PIO13") (pintype "bidirectional"))
    )
    (net (code "58") (name "unconnected-(U4-PadPIO14)") (class "Default")
      (node (ref "U4") (pin "PIO14") (pinfunction "PIO14_PIO14") (pintype "bidirectional"))
    )
    (net (code "59") (name "unconnected-(U4-PadPIO15)") (class "Default")
      (node (ref "U4") (pin "PIO15") (pinfunction "PIO15_PIO15") (pintype "bidirectional"))
    )
    (net (code "60") (name "unconnected-(U4-PadRES1)") (class "Default")
      (node (ref "U4") (pin "RES1") (pinfunction "RES1_RES1") (pintype "bidirectional"))
    )
    (net (code "61") (name "unconnected-(U4-PadRES2)") (class "Default")
      (node (ref "U4") (pin "RES2") (pinfunction "RES2_RES2") (pintype "bidirectional"))
    )
    (net (code "62") (name "unconnected-(U4-PadRES3)") (class "Default")
      (node (ref "U4") (pin "RES3") (pinfunction "RES3_RES3") (pintype "bidirectional"))
    )
    (net (code "63") (name "unconnected-(U4-PadRES4)") (class "Default")
      (node (ref "U4") (pin "RES4") (pinfunction "RES4_RES4") (pintype "bidirectional"))
    )
    (net (code "64") (name "unconnected-(U4-PadRES5)") (class "Default")
      (node (ref "U4") (pin "RES5") (pinfunction "RES5_RES5") (pintype "bidirectional"))
    )
    (net (code "65") (name "unconnected-(U4-PadRES6)") (class "Default")
      (node (ref "U4") (pin "RES6") (pinfunction "RES6_RES6") (pintype "bidirectional"))
    )
    (net (code "66") (name "unconnected-(U4-PadRES7)") (class "Default")
      (node (ref "U4") (pin "RES7") (pinfunction "RES7_RES7") (pintype "bidirectional"))
    )
    (net (code "67") (name "unconnected-(U4-PadRESET_N)") (class "Default")
      (node (ref "U4") (pin "RESET_N") (pinfunction "RESET_N_RESET_N") (pintype "bidirectional"))
    )
    (net (code "68") (name "unconnected-(U4-PadSAFEBOOT_N)") (class "Default")
      (node (ref "U4") (pin "SAFEBOOT_N") (pinfunction "SAFEBOOT_N_SAFEBOOT_N") (pintype "bidirectional"))
    )
    (net (code "69") (name "unconnected-(U4-PadSCL)") (class "Default")
      (node (ref "U4") (pin "SCL") (pinfunction "SCL_SCL") (pintype "bidirectional"))
    )
    (net (code "70") (name "unconnected-(U4-PadSDA)") (class "Default")
      (node (ref "U4") (pin "SDA") (pinfunction "SDA_SDA") (pintype "bidirectional"))
    )
    (net (code "71") (name "unconnected-(U4-PadSQI_CLK)") (class "Default")
      (node (ref "U4") (pin "SQI_CLK") (pinfunction "SQI_CLK_SQI_CLK") (pintype "bidirectional"))
    )
    (net (code "72") (name "unconnected-(U4-PadSQI_CS_N)") (class "Default")
      (node (ref "U4") (pin "SQI_CS_N") (pinfunction "SQI_CS_N_SQI_CS_N") (pintype "bidirectional"))
    )
    (net (code "73") (name "unconnected-(U4-PadSQI_D0)") (class "Default")
      (node (ref "U4") (pin "SQI_D0") (pinfunction "SQI_D0_SQI_D0") (pintype "bidirectional"))
    )
    (net (code "74") (name "unconnected-(U4-PadSQI_D1)") (class "Default")
      (node (ref "U4") (pin "SQI_D1") (pinfunction "SQI_D1_SQI_D1") (pintype "bidirectional"))
    )
    (net (code "75") (name "unconnected-(U4-PadSQI_D2)") (class "Default")
      (node (ref "U4") (pin "SQI_D2") (pinfunction "SQI_D2_SQI_D2") (pintype "bidirectional"))
    )
    (net (code "76") (name "unconnected-(U4-PadSQI_D3)") (class "Default")
      (node (ref "U4") (pin "SQI_D3") (pinfunction "SQI_D3_SQI_D3") (pintype "bidirectional"))
    )
    (net (code "77") (name "unconnected-(U5-PadCLK0)") (class "Default")
      (node (ref "U5") (pin "CLK0") (pinfunction "CLK0_CLK0") (pintype "bidirectional"))
    )
    (net (code "78") (name "unconnected-(U5-PadCLK2)") (class "Default")
      (node (ref "U5") (pin "CLK2") (pinfunction "CLK2_CLK2") (pintype "bidirectional"))
    )
    (net (code "79") (name "unconnected-(U5-PadCLK3)") (class "Default")
      (node (ref "U5") (pin "CLK3") (pinfunction "CLK3_CLK3") (pintype "bidirectional"))
    )
    (net (code "80") (name "unconnected-(U5-PadCLK4)") (class "Default")
      (node (ref "U5") (pin "CLK4") (pinfunction "CLK4_CLK4") (pintype "bidirectional"))
    )
    (net (code "81") (name "unconnected-(U5-PadCLK6)") (class "Default")
      (node (ref "U5") (pin "CLK6") (pinfunction "CLK6_CLK6") (pintype "bidirectional"))
    )
    (net (code "82") (name "unconnected-(U5-PadCLK7)") (class "Default")
      (node (ref "U5") (pin "CLK7") (pinfunction "CLK7_CLK7") (pintype "bidirectional"))
    )
    (net (code "83") (name "unconnected-(U5-PadXB)") (class "Default")
      (node (ref "U5") (pin "XB") (pinfunction "XB_XB") (pintype "bidirectional"))
    )
  )
)
